# power-supply-tests.net
KiCad netlist of a schematic drawn in EAGLE
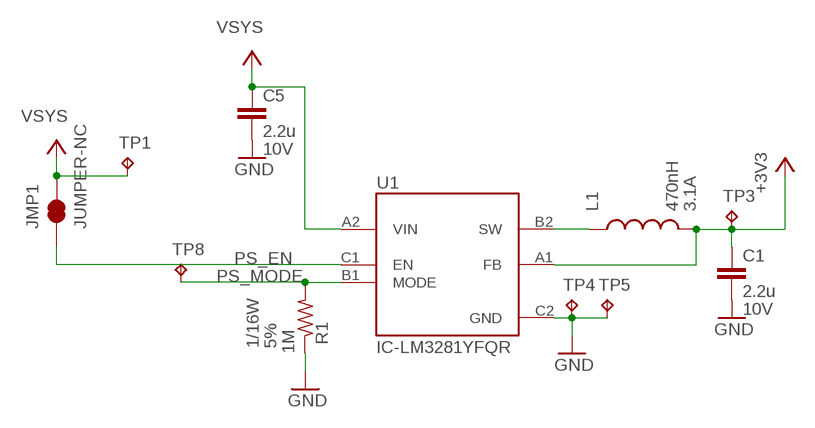
[diagram p0: schematic, sheet 1]

(export (version "E")
  (design (tool "Eeschema 10.0.6"))
  (components
    (comp (ref "C1")
      (value "2.2u")
      (footprint "eagle-import:C0603")
      (fields (field (name "MPN") "GRM188R71A225KE15D") (field (name "VOLTHIGH") "10V"))
      (libsource (lib "eagle-import") (part "CAP-0603-2.2U-10V-01"))
    )
    (comp (ref "C5")
      (value "2.2u")
      (footprint "eagle-import:C0603")
      (fields (field (name "MPN") "GRM188R71A225KE15D") (field (name "VOLTHIGH") "10V"))
      (libsource (lib "eagle-import") (part "CAP-0603-2.2U-10V-01"))
    )
    (comp (ref "JMP1")
      (value "JUMPER-NC")
      (footprint "eagle-import:JUMPER-ROUND-NC")
      (libsource (lib "eagle-import") (part "JUMPER-NC"))
    )
    (comp (ref "L1")
      (value "470nH")
      (footprint "eagle-import:INDC2012X100N")
      (fields
        (field (name "CURRENT") "3.1A")
        (field (name "MF") "Murata")
        (field (name "MPN") "LQM21PNR47MGHL‎")
      )
      (libsource (lib "eagle-import") (part "IND-0805-3.1A-60MOHM"))
    )
    (comp (ref "R1")
      (value "1M")
      (footprint "eagle-import:R0402-M")
      (fields
        (field (name "MPN") "RC0402JR-071ML")
        (field (name "POWER") "1/16W")
        (field (name "TOLERANCE") "5%")
      )
      (libsource (lib "eagle-import") (part "RES-0402-1M-5%"))
    )
    (comp (ref "TP1")
      (value "HEADER-1")
      (footprint "eagle-import:CON-HEADER-1X1-POGO-1P9")
      (libsource (lib "eagle-import") (part "HEADER-1"))
    )
    (comp (ref "TP3")
      (value "HEADER-1")
      (footprint "eagle-import:CON-HEADER-1X1-POGO-1P9")
      (libsource (lib "eagle-import") (part "HEADER-1"))
    )
    (comp (ref "TP4")
      (value "HEADER-1")
      (footprint "eagle-import:CON-HEADER-1X1-POGO-1P9")
      (libsource (lib "eagle-import") (part "HEADER-1"))
    )
    (comp (ref "TP5")
      (value "HEADER-1")
      (footprint "eagle-import:CON-HEADER-1X1-POGO-1P9")
      (libsource (lib "eagle-import") (part "HEADER-1"))
    )
    (comp (ref "TP8")
      (value "HEADER-1")
      (footprint "eagle-import:CON-HEADER-1X1-POGO-1P9")
      (libsource (lib "eagle-import") (part "HEADER-1"))
    )
    (comp (ref "U1")
      (value "IC-LM3281YFQR")
      (footprint "eagle-import:BGA6N40P2X3_116X143X67N")
      (fields (field (name "MF") "Texas Instruments") (field (name "MPN") "LM3281YFQR"))
      (libsource (lib "eagle-import") (part "IC-LM3281YFQR"))
    )
  )
  (nets
    (net (code "1") (name "+3V3") (class "Default")
      (node (ref "C1") (pin "1") (pinfunction "1_1") (pintype "passive"))
      (node (ref "L1") (pin "2") (pinfunction "2_2") (pintype "passive"))
      (node (ref "TP3") (pin "1") (pinfunction "TP_1") (pintype "input"))
      (node (ref "U1") (pin "A1") (pinfunction "FB_A1") (pintype "input"))
    )
    (net (code "2") (name "/PS_EN") (class "Default")
      (node (ref "JMP1") (pin "P$1") (pinfunction "1_P$1") (pintype "passive"))
      (node (ref "U1") (pin "C1") (pinfunction "EN_C1") (pintype "input"))
    )
    (net (code "3") (name "/PS_MODE") (class "Default")
      (node (ref "R1") (pin "2") (pinfunction "2_2") (pintype "passive"))
      (node (ref "TP8") (pin "1") (pinfunction "TP_1") (pintype "input"))
      (node (ref "U1") (pin "B1") (pinfunction "MODE_B1") (pintype "input"))
    )
    (net (code "4") (name "GND") (class "Default")
      (node (ref "C1") (pin "2") (pinfunction "2_2") (pintype "passive"))
      (node (ref "C5") (pin "2") (pinfunction "2_2") (pintype "passive"))
      (node (ref "R1") (pin "1") (pinfunction "1_1") (pintype "passive"))
      (node (ref "TP4") (pin "1") (pinfunction "TP_1") (pintype "input"))
      (node (ref "TP5") (pin "1") (pinfunction "TP_1") (pintype "input"))
      (node (ref "U1") (pin "C2") (pinfunction "GND_C2") (pintype "power_in"))
    )
    (net (code "5") (name "Net-(U1-SW)") (class "Default")
      (node (ref "L1") (pin "1") (pinfunction "1_1") (pintype "passive"))
      (node (ref "U1") (pin "B2") (pinfunction "SW_B2") (pintype "output"))
    )
    (net (code "6") (name "VSYS") (class "Default")
      (node (ref "C5") (pin "1") (pinfunction "1_1") (pintype "passive"))
      (node (ref "JMP1") (pin "P$2") (pinfunction "2_P$2") (pintype "passive"))
      (node (ref "TP1") (pin "1") (pinfunction "TP_1") (pintype "input"))
      (node (ref "U1") (pin "A2") (pinfunction "VIN_A2") (pintype "input"))
    )
  )
)
